# QUTMS-TSAL-V00-S04.net
KiCad netlist of a schematic drawn in Altium Designer
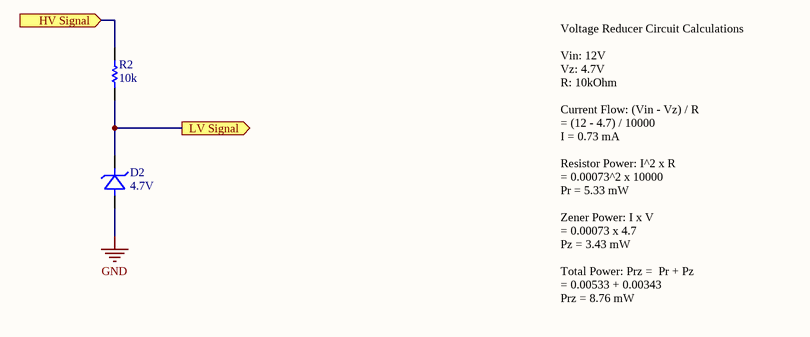
[diagram p0: QUTMS-TSAL-V00-S04.SchDoc]

(export (version "E")
  (design (tool "Eeschema 10.0.6"))
  (components
    (comp (ref "D2")
      (value "4.7V")
      (footprint "SOD123")
      (description "MMSZ4688T1G -  Zener Single Diode, 4.7 V, 500 mW, SOD-123, 5 %, 2 Pins, 150 °C")
      (libsource (lib "QUTMS_DiodeLibrary") (part "MMSZ4688T1G"))
    )
    (comp (ref "R2")
      (value "10k")
      (footprint "Res_ThinFilm_0603")
      (description "Resistor, SMD, 10k, 0.1W, 5%, 0603")
      (libsource (lib "StandardResistors") (part "10k 5% 0603"))
    )
  )
  (nets
    (net (code "1") (name "/HV Signal") (class "Default")
      (node (ref "R2") (pin "2") (pinfunction "2_2") (pintype "passive"))
    )
    (net (code "2") (name "/LV Signal") (class "Default")
      (node (ref "D2") (pin "K") (pinfunction "Cathode_K") (pintype "passive"))
      (node (ref "R2") (pin "1") (pinfunction "1_1") (pintype "passive"))
    )
    (net (code "3") (name "GND") (class "Default")
      (node (ref "D2") (pin "A") (pinfunction "Anode_A") (pintype "passive"))
    )
  )
)
